# PX4FMUv2_3_SCH1.net
KiCad netlist of a schematic drawn in Altium Designer
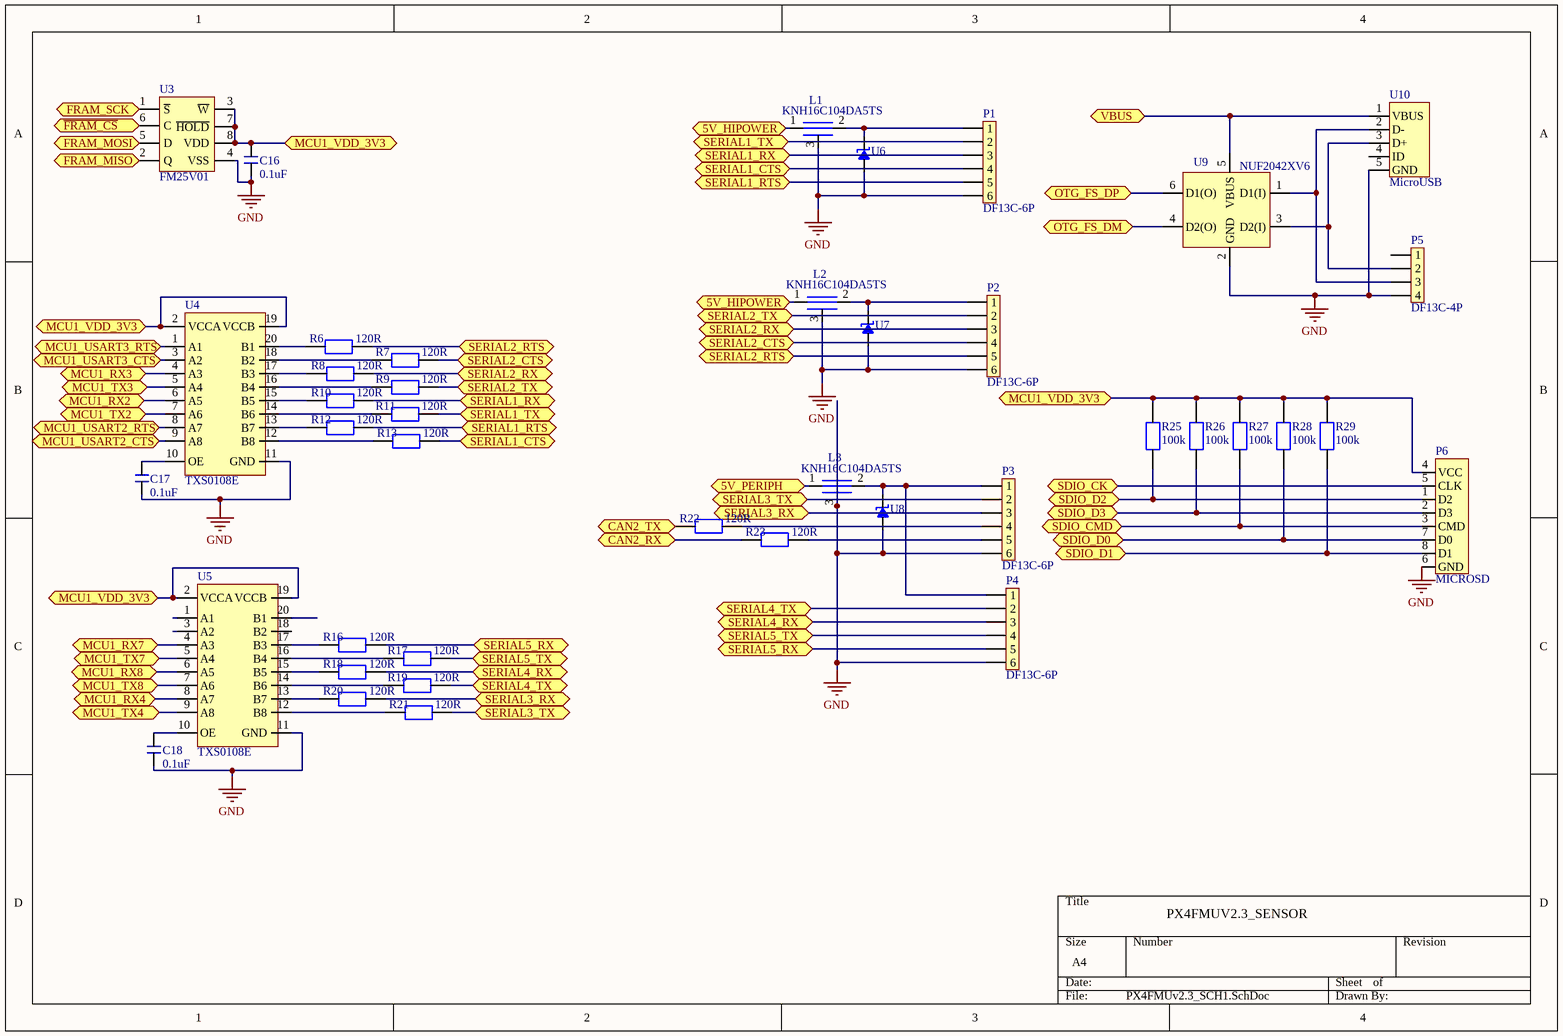
[diagram p0: PX4FMUv2.3_SCH1.SchDoc]

(export (version "E")
  (design (tool "Eeschema 10.0.6"))
  (components
    (comp (ref "C16") (value "0.1uF") (footprint "C 0402") (libsource (lib "px4_SCHLIB") (part "CAP_0402")))
    (comp (ref "C17") (value "0.1uF") (footprint "C 0402") (libsource (lib "px4_SCHLIB") (part "CAP_0402")))
    (comp (ref "C18") (value "0.1uF") (footprint "C 0402") (libsource (lib "px4_SCHLIB") (part "CAP_0402")))
    (comp (ref "L1")
      (value "KNH16C104DA5TS")
      (footprint "KYOCERA-KNH16-DA")
      (libsource (lib "px4_SCHLIB") (part "KNH16C104DA5TS"))
    )
    (comp (ref "L2")
      (value "KNH16C104DA5TS")
      (footprint "KYOCERA-KNH16-DA")
      (libsource (lib "px4_SCHLIB") (part "KNH16C104DA5TS"))
    )
    (comp (ref "L3")
      (value "KNH16C104DA5TS")
      (footprint "KYOCERA-KNH16-DA")
      (libsource (lib "px4_SCHLIB") (part "KNH16C104DA5TS"))
    )
    (comp (ref "P1")
      (value "DF13C-6P")
      (footprint "MX 1.25-LS-6P")
      (libsource (lib "px4_SCHLIB") (part "DF13C-6P"))
    )
    (comp (ref "P2")
      (value "DF13C-6P")
      (footprint "MX 1.25-LS-6P")
      (libsource (lib "px4_SCHLIB") (part "DF13C-6P"))
    )
    (comp (ref "P3")
      (value "DF13C-6P")
      (footprint "MX 1.25-LS-6P")
      (libsource (lib "px4_SCHLIB") (part "DF13C-6P"))
    )
    (comp (ref "P4")
      (value "DF13C-6P")
      (footprint "MX 1.25-LS-6P")
      (libsource (lib "px4_SCHLIB") (part "DF13C-6P"))
    )
    (comp (ref "P5")
      (value "DF13C-4P")
      (footprint "MX 1.25-LS-4P")
      (libsource (lib "px4_SCHLIB") (part "DF13C-4P"))
    )
    (comp (ref "P6") (value "MICROSD") (footprint "microSD") (libsource (lib "px4_SCHLIB") (part "MICROSD")))
    (comp (ref "R6") (value "120R") (footprint "0402R") (libsource (lib "px4_SCHLIB") (part "Res_0402")))
    (comp (ref "R7") (value "120R") (footprint "0402R") (libsource (lib "px4_SCHLIB") (part "Res_0402")))
    (comp (ref "R8") (value "120R") (footprint "0402R") (libsource (lib "px4_SCHLIB") (part "Res_0402")))
    (comp (ref "R9") (value "120R") (footprint "0402R") (libsource (lib "px4_SCHLIB") (part "Res_0402")))
    (comp (ref "R10") (value "120R") (footprint "0402R") (libsource (lib "px4_SCHLIB") (part "Res_0402")))
    (comp (ref "R11") (value "120R") (footprint "0402R") (libsource (lib "px4_SCHLIB") (part "Res_0402")))
    (comp (ref "R12") (value "120R") (footprint "0402R") (libsource (lib "px4_SCHLIB") (part "Res_0402")))
    (comp (ref "R13") (value "120R") (footprint "0402R") (libsource (lib "px4_SCHLIB") (part "Res_0402")))
    (comp (ref "R16") (value "120R") (footprint "0402R") (libsource (lib "px4_SCHLIB") (part "Res_0402")))
    (comp (ref "R17") (value "120R") (footprint "0402R") (libsource (lib "px4_SCHLIB") (part "Res_0402")))
    (comp (ref "R18") (value "120R") (footprint "0402R") (libsource (lib "px4_SCHLIB") (part "Res_0402")))
    (comp (ref "R19") (value "120R") (footprint "0402R") (libsource (lib "px4_SCHLIB") (part "Res_0402")))
    (comp (ref "R20") (value "120R") (footprint "0402R") (libsource (lib "px4_SCHLIB") (part "Res_0402")))
    (comp (ref "R21") (value "120R") (footprint "0402R") (libsource (lib "px4_SCHLIB") (part "Res_0402")))
    (comp (ref "R22") (value "120R") (footprint "0402R") (libsource (lib "px4_SCHLIB") (part "Res_0402")))
    (comp (ref "R23") (value "120R") (footprint "0402R") (libsource (lib "px4_SCHLIB") (part "Res_0402")))
    (comp (ref "R25") (value "100k") (footprint "0402R") (libsource (lib "px4_SCHLIB") (part "Res_0402")))
    (comp (ref "R26") (value "100k") (footprint "0402R") (libsource (lib "px4_SCHLIB") (part "Res_0402")))
    (comp (ref "R27") (value "100k") (footprint "0402R") (libsource (lib "px4_SCHLIB") (part "Res_0402")))
    (comp (ref "R28") (value "100k") (footprint "0402R") (libsource (lib "px4_SCHLIB") (part "Res_0402")))
    (comp (ref "R29") (value "100k") (footprint "0402R") (libsource (lib "px4_SCHLIB") (part "Res_0402")))
    (comp (ref "U3") (value "FM25V01") (footprint "SOIC8") (libsource (lib "px4_SCHLIB") (part "FM25V01")))
    (comp (ref "U4")
      (value "TXS0108E")
      (footprint "PQFN50P450X350X100_HS-21N")
      (libsource (lib "px4_SCHLIB") (part "TXS0108E"))
    )
    (comp (ref "U5")
      (value "TXS0108E")
      (footprint "PQFN50P450X350X100_HS-21N")
      (libsource (lib "px4_SCHLIB") (part "TXS0108E"))
    )
    (comp (ref "U6")
      (value "PESD0402-140")
      (footprint "0402-TVS")
      (libsource (lib "px4_SCHLIB") (part "PESD0402-140"))
    )
    (comp (ref "U7")
      (value "PESD0402-140")
      (footprint "0402-TVS")
      (libsource (lib "px4_SCHLIB") (part "PESD0402-140"))
    )
    (comp (ref "U8")
      (value "PESD0402-140")
      (footprint "0402-TVS")
      (libsource (lib "px4_SCHLIB") (part "PESD0402-140"))
    )
    (comp (ref "U9")
      (value "NUF2042XV6")
      (footprint "SOT563-6")
      (libsource (lib "px4_SCHLIB") (part "NUF2042XV6"))
    )
    (comp (ref "U10")
      (value "MicroUSB")
      (footprint "USB-MICRO_E")
      (libsource (lib "px4_SCHLIB") (part "MicroUSB_SMD"))
    )
  )
  (nets
    (net (code "1") (name "/5V_HIPOWER") (class "Default")
      (node (ref "L1") (pin "1") (pinfunction "1_1") (pintype "passive"))
      (node (ref "L2") (pin "1") (pinfunction "1_1") (pintype "passive"))
    )
    (net (code "2") (name "/5V_PERIPH") (class "Default")
      (node (ref "L3") (pin "1") (pinfunction "1_1") (pintype "passive"))
    )
    (net (code "3") (name "/CAN2_RX") (class "Default")
      (node (ref "R23") (pin "1") (pinfunction "1_1") (pintype "passive"))
    )
    (net (code "4") (name "/CAN2_TX") (class "Default")
      (node (ref "R22") (pin "1") (pinfunction "1_1") (pintype "passive"))
    )
    (net (code "5") (name "/FRAM_MISO") (class "Default")
      (node (ref "U3") (pin "2") (pinfunction "Q_2") (pintype "passive"))
    )
    (net (code "6") (name "/FRAM_MOSI") (class "Default")
      (node (ref "U3") (pin "5") (pinfunction "D_5") (pintype "passive"))
    )
    (net (code "7") (name "/FRAM_SCK") (class "Default")
      (node (ref "U3") (pin "1") (pinfunction "S_1") (pintype "passive"))
    )
    (net (code "8") (name "/MCU1_RX2") (class "Default")
      (node (ref "U4") (pin "6") (pinfunction "A5_6") (pintype "passive"))
    )
    (net (code "9") (name "/MCU1_RX3") (class "Default")
      (node (ref "U4") (pin "4") (pinfunction "A3_4") (pintype "passive"))
    )
    (net (code "10") (name "/MCU1_RX4") (class "Default")
      (node (ref "U5") (pin "8") (pinfunction "A7_8") (pintype "passive"))
    )
    (net (code "11") (name "/MCU1_RX7") (class "Default")
      (node (ref "U5") (pin "4") (pinfunction "A3_4") (pintype "passive"))
    )
    (net (code "12") (name "/MCU1_RX8") (class "Default")
      (node (ref "U5") (pin "6") (pinfunction "A5_6") (pintype "passive"))
    )
    (net (code "13") (name "/MCU1_TX2") (class "Default")
      (node (ref "U4") (pin "7") (pinfunction "A6_7") (pintype "passive"))
    )
    (net (code "14") (name "/MCU1_TX3") (class "Default")
      (node (ref "U4") (pin "5") (pinfunction "A4_5") (pintype "passive"))
    )
    (net (code "15") (name "/MCU1_TX4") (class "Default")
      (node (ref "U5") (pin "9") (pinfunction "A8_9") (pintype "passive"))
    )
    (net (code "16") (name "/MCU1_TX7") (class "Default")
      (node (ref "U5") (pin "5") (pinfunction "A4_5") (pintype "passive"))
    )
    (net (code "17") (name "/MCU1_TX8") (class "Default")
      (node (ref "U5") (pin "7") (pinfunction "A6_7") (pintype "passive"))
    )
    (net (code "18") (name "/MCU1_USART2_CTS") (class "Default")
      (node (ref "U4") (pin "9") (pinfunction "A8_9") (pintype "passive"))
    )
    (net (code "19") (name "/MCU1_USART2_RTS") (class "Default")
      (node (ref "U4") (pin "8") (pinfunction "A7_8") (pintype "passive"))
    )
    (net (code "20") (name "/MCU1_USART3_CTS") (class "Default")
      (node (ref "U4") (pin "3") (pinfunction "A2_3") (pintype "passive"))
    )
    (net (code "21") (name "/MCU1_USART3_RTS") (class "Default")
      (node (ref "U4") (pin "1") (pinfunction "A1_1") (pintype "passive"))
    )
    (net (code "22") (name "/MCU1_VDD_3V3") (class "Default")
      (node (ref "C16") (pin "1") (pinfunction "1_1") (pintype "passive"))
      (node (ref "P6") (pin "4") (pinfunction "VCC_4") (pintype "passive"))
      (node (ref "R25") (pin "2") (pinfunction "2_2") (pintype "passive"))
      (node (ref "R26") (pin "2") (pinfunction "2_2") (pintype "passive"))
      (node (ref "R27") (pin "2") (pinfunction "2_2") (pintype "passive"))
      (node (ref "R28") (pin "2") (pinfunction "2_2") (pintype "passive"))
      (node (ref "R29") (pin "2") (pinfunction "2_2") (pintype "passive"))
      (node (ref "U3") (pin "3") (pinfunction "W_3") (pintype "passive"))
      (node (ref "U3") (pin "7") (pinfunction "HOLD_7") (pintype "passive"))
      (node (ref "U3") (pin "8") (pinfunction "VDD_8") (pintype "passive"))
      (node (ref "U4") (pin "19") (pinfunction "VCCB_19") (pintype "passive"))
      (node (ref "U4") (pin "2") (pinfunction "VCCA_2") (pintype "passive"))
      (node (ref "U5") (pin "19") (pinfunction "VCCB_19") (pintype "passive"))
      (node (ref "U5") (pin "2") (pinfunction "VCCA_2") (pintype "passive"))
    )
    (net (code "23") (name "/OTG_FS_DM") (class "Default")
      (node (ref "U9") (pin "4") (pinfunction "D2(O)_4") (pintype "passive"))
    )
    (net (code "24") (name "/OTG_FS_DP") (class "Default")
      (node (ref "U9") (pin "6") (pinfunction "D1(O)_6") (pintype "passive"))
    )
    (net (code "25") (name "/SDIO_CK") (class "Default")
      (node (ref "P6") (pin "5") (pinfunction "CLK_5") (pintype "passive"))
    )
    (net (code "26") (name "/SDIO_CMD") (class "Default")
      (node (ref "P6") (pin "3") (pinfunction "CMD_3") (pintype "passive"))
      (node (ref "R27") (pin "1") (pinfunction "1_1") (pintype "passive"))
    )
    (net (code "27") (name "/SDIO_D0") (class "Default")
      (node (ref "P6") (pin "7") (pinfunction "D0_7") (pintype "passive"))
      (node (ref "R28") (pin "1") (pinfunction "1_1") (pintype "passive"))
    )
    (net (code "28") (name "/SDIO_D1") (class "Default")
      (node (ref "P6") (pin "8") (pinfunction "D1_8") (pintype "passive"))
      (node (ref "R29") (pin "1") (pinfunction "1_1") (pintype "passive"))
    )
    (net (code "29") (name "/SDIO_D2") (class "Default")
      (node (ref "P6") (pin "1") (pinfunction "D2_1") (pintype "passive"))
      (node (ref "R25") (pin "1") (pinfunction "1_1") (pintype "passive"))
    )
    (net (code "30") (name "/SDIO_D3") (class "Default")
      (node (ref "P6") (pin "2") (pinfunction "D3_2") (pintype "passive"))
      (node (ref "R26") (pin "1") (pinfunction "1_1") (pintype "passive"))
    )
    (net (code "31") (name "/SERIAL1_CTS") (class "Default")
      (node (ref "P1") (pin "4") (pinfunction "4_4") (pintype "passive"))
      (node (ref "R13") (pin "2") (pinfunction "2_2") (pintype "passive"))
    )
    (net (code "32") (name "/SERIAL1_RTS") (class "Default")
      (node (ref "P1") (pin "5") (pinfunction "5_5") (pintype "passive"))
      (node (ref "R12") (pin "2") (pinfunction "2_2") (pintype "passive"))
    )
    (net (code "33") (name "/SERIAL1_RX") (class "Default")
      (node (ref "P1") (pin "3") (pinfunction "3_3") (pintype "passive"))
      (node (ref "R10") (pin "2") (pinfunction "2_2") (pintype "passive"))
    )
    (net (code "34") (name "/SERIAL1_TX") (class "Default")
      (node (ref "P1") (pin "2") (pinfunction "2_2") (pintype "passive"))
      (node (ref "R11") (pin "2") (pinfunction "2_2") (pintype "passive"))
    )
    (net (code "35") (name "/SERIAL2_CTS") (class "Default")
      (node (ref "P2") (pin "4") (pinfunction "4_4") (pintype "passive"))
      (node (ref "R7") (pin "2") (pinfunction "2_2") (pintype "passive"))
    )
    (net (code "36") (name "/SERIAL2_RTS") (class "Default")
      (node (ref "P2") (pin "5") (pinfunction "5_5") (pintype "passive"))
      (node (ref "R6") (pin "2") (pinfunction "2_2") (pintype "passive"))
    )
    (net (code "37") (name "/SERIAL2_RX") (class "Default")
      (node (ref "P2") (pin "3") (pinfunction "3_3") (pintype "passive"))
      (node (ref "R8") (pin "2") (pinfunction "2_2") (pintype "passive"))
    )
    (net (code "38") (name "/SERIAL2_TX") (class "Default")
      (node (ref "P2") (pin "2") (pinfunction "2_2") (pintype "passive"))
      (node (ref "R9") (pin "2") (pinfunction "2_2") (pintype "passive"))
    )
    (net (code "39") (name "/SERIAL3_RX") (class "Default")
      (node (ref "P3") (pin "3") (pinfunction "3_3") (pintype "passive"))
      (node (ref "R20") (pin "2") (pinfunction "2_2") (pintype "passive"))
    )
    (net (code "40") (name "/SERIAL3_TX") (class "Default")
      (node (ref "P3") (pin "2") (pinfunction "2_2") (pintype "passive"))
      (node (ref "R21") (pin "2") (pinfunction "2_2") (pintype "passive"))
    )
    (net (code "41") (name "/SERIAL4_RX") (class "Default")
      (node (ref "P4") (pin "3") (pinfunction "3_3") (pintype "passive"))
      (node (ref "R18") (pin "2") (pinfunction "2_2") (pintype "passive"))
    )
    (net (code "42") (name "/SERIAL4_TX") (class "Default")
      (node (ref "P4") (pin "2") (pinfunction "2_2") (pintype "passive"))
      (node (ref "R19") (pin "2") (pinfunction "2_2") (pintype "passive"))
    )
    (net (code "43") (name "/SERIAL5_RX") (class "Default")
      (node (ref "P4") (pin "5") (pinfunction "5_5") (pintype "passive"))
      (node (ref "R16") (pin "2") (pinfunction "2_2") (pintype "passive"))
    )
    (net (code "44") (name "/SERIAL5_TX") (class "Default")
      (node (ref "P4") (pin "4") (pinfunction "4_4") (pintype "passive"))
      (node (ref "R17") (pin "2") (pinfunction "2_2") (pintype "passive"))
    )
    (net (code "45") (name "/VBUS") (class "Default")
      (node (ref "U10") (pin "1") (pinfunction "VBUS_1") (pintype "passive"))
      (node (ref "U9") (pin "5") (pinfunction "VBUS_5") (pintype "passive"))
    )
    (net (code "46") (name "/~{FRAM_CS}") (class "Default")
      (node (ref "U3") (pin "6") (pinfunction "C_6") (pintype "passive"))
    )
    (net (code "47") (name "GND") (class "Default")
      (node (ref "C16") (pin "2") (pinfunction "2_2") (pintype "passive"))
      (node (ref "C17") (pin "2") (pinfunction "2_2") (pintype "passive"))
      (node (ref "C18") (pin "2") (pinfunction "2_2") (pintype "passive"))
      (node (ref "L1") (pin "3") (pinfunction "3_3") (pintype "passive"))
      (node (ref "L2") (pin "3") (pinfunction "3_3") (pintype "passive"))
      (node (ref "L3") (pin "3") (pinfunction "3_3") (pintype "passive"))
      (node (ref "P1") (pin "6") (pinfunction "6_6") (pintype "passive"))
      (node (ref "P2") (pin "6") (pinfunction "6_6") (pintype "passive"))
      (node (ref "P3") (pin "6") (pinfunction "6_6") (pintype "passive"))
      (node (ref "P4") (pin "6") (pinfunction "6_6") (pintype "passive"))
      (node (ref "P5") (pin "4") (pinfunction "4_4") (pintype "passive"))
      (node (ref "P6") (pin "6") (pinfunction "GND_6") (pintype "passive"))
      (node (ref "U10") (pin "5") (pinfunction "GND_5") (pintype "passive"))
      (node (ref "U3") (pin "4") (pinfunction "VSS_4") (pintype "passive"))
      (node (ref "U4") (pin "11") (pinfunction "GND_11") (pintype "passive"))
      (node (ref "U5") (pin "11") (pinfunction "GND_11") (pintype "passive"))
      (node (ref "U6") (pin "1") (pinfunction "1_1") (pintype "passive"))
      (node (ref "U7") (pin "1") (pinfunction "1_1") (pintype "passive"))
      (node (ref "U8") (pin "1") (pinfunction "1_1") (pintype "passive"))
      (node (ref "U9") (pin "2") (pinfunction "GND_2") (pintype "passive"))
    )
    (net (code "48") (name "Net-(L1-Pad2)") (class "Default")
      (node (ref "L1") (pin "2") (pinfunction "2_2") (pintype "passive"))
      (node (ref "P1") (pin "1") (pinfunction "1_1") (pintype "passive"))
      (node (ref "U6") (pin "2") (pinfunction "2_2") (pintype "passive"))
    )
    (net (code "49") (name "Net-(L2-Pad2)") (class "Default")
      (node (ref "L2") (pin "2") (pinfunction "2_2") (pintype "passive"))
      (node (ref "P2") (pin "1") (pinfunction "1_1") (pintype "passive"))
      (node (ref "U7") (pin "2") (pinfunction "2_2") (pintype "passive"))
    )
    (net (code "50") (name "Net-(L3-Pad2)") (class "Default")
      (node (ref "L3") (pin "2") (pinfunction "2_2") (pintype "passive"))
      (node (ref "P3") (pin "1") (pinfunction "1_1") (pintype "passive"))
      (node (ref "P4") (pin "1") (pinfunction "1_1") (pintype "passive"))
      (node (ref "U8") (pin "2") (pinfunction "2_2") (pintype "passive"))
    )
    (net (code "51") (name "Net-(P3-Pad4)") (class "Default")
      (node (ref "P3") (pin "4") (pinfunction "4_4") (pintype "passive"))
      (node (ref "R22") (pin "2") (pinfunction "2_2") (pintype "passive"))
    )
    (net (code "52") (name "Net-(P3-Pad5)") (class "Default")
      (node (ref "P3") (pin "5") (pinfunction "5_5") (pintype "passive"))
      (node (ref "R23") (pin "2") (pinfunction "2_2") (pintype "passive"))
    )
    (net (code "53") (name "Net-(U4-B1)") (class "Default")
      (node (ref "R6") (pin "1") (pinfunction "1_1") (pintype "passive"))
      (node (ref "U4") (pin "20") (pinfunction "B1_20") (pintype "passive"))
    )
    (net (code "54") (name "Net-(U4-B2)") (class "Default")
      (node (ref "R7") (pin "1") (pinfunction "1_1") (pintype "passive"))
      (node (ref "U4") (pin "18") (pinfunction "B2_18") (pintype "passive"))
    )
    (net (code "55") (name "Net-(U4-B3)") (class "Default")
      (node (ref "R8") (pin "1") (pinfunction "1_1") (pintype "passive"))
      (node (ref "U4") (pin "17") (pinfunction "B3_17") (pintype "passive"))
    )
    (net (code "56") (name "Net-(U4-B4)") (class "Default")
      (node (ref "R9") (pin "1") (pinfunction "1_1") (pintype "passive"))
      (node (ref "U4") (pin "16") (pinfunction "B4_16") (pintype "passive"))
    )
    (net (code "57") (name "Net-(U4-B5)") (class "Default")
      (node (ref "R10") (pin "1") (pinfunction "1_1") (pintype "passive"))
      (node (ref "U4") (pin "15") (pinfunction "B5_15") (pintype "passive"))
    )
    (net (code "58") (name "Net-(U4-B6)") (class "Default")
      (node (ref "R11") (pin "1") (pinfunction "1_1") (pintype "passive"))
      (node (ref "U4") (pin "14") (pinfunction "B6_14") (pintype "passive"))
    )
    (net (code "59") (name "Net-(U4-B7)") (class "Default")
      (node (ref "R12") (pin "1") (pinfunction "1_1") (pintype "passive"))
      (node (ref "U4") (pin "13") (pinfunction "B7_13") (pintype "passive"))
    )
    (net (code "60") (name "Net-(U4-B8)") (class "Default")
      (node (ref "R13") (pin "1") (pinfunction "1_1") (pintype "passive"))
      (node (ref "U4") (pin "12") (pinfunction "B8_12") (pintype "passive"))
    )
    (net (code "61") (name "Net-(U4-OE)") (class "Default")
      (node (ref "C17") (pin "1") (pinfunction "1_1") (pintype "passive"))
      (node (ref "U4") (pin "10") (pinfunction "OE_10") (pintype "passive"))
    )
    (net (code "62") (name "Net-(U5-B3)") (class "Default")
      (node (ref "R16") (pin "1") (pinfunction "1_1") (pintype "passive"))
      (node (ref "U5") (pin "17") (pinfunction "B3_17") (pintype "passive"))
    )
    (net (code "63") (name "Net-(U5-B4)") (class "Default")
      (node (ref "R17") (pin "1") (pinfunction "1_1") (pintype "passive"))
      (node (ref "U5") (pin "16") (pinfunction "B4_16") (pintype "passive"))
    )
    (net (code "64") (name "Net-(U5-B5)") (class "Default")
      (node (ref "R18") (pin "1") (pinfunction "1_1") (pintype "passive"))
      (node (ref "U5") (pin "15") (pinfunction "B5_15") (pintype "passive"))
    )
    (net (code "65") (name "Net-(U5-B6)") (class "Default")
      (node (ref "R19") (pin "1") (pinfunction "1_1") (pintype "passive"))
      (node (ref "U5") (pin "14") (pinfunction "B6_14") (pintype "passive"))
    )
    (net (code "66") (name "Net-(U5-B7)") (class "Default")
      (node (ref "R20") (pin "1") (pinfunction "1_1") (pintype "passive"))
      (node (ref "U5") (pin "13") (pinfunction "B7_13") (pintype "passive"))
    )
    (net (code "67") (name "Net-(U5-B8)") (class "Default")
      (node (ref "R21") (pin "1") (pinfunction "1_1") (pintype "passive"))
      (node (ref "U5") (pin "12") (pinfunction "B8_12") (pintype "passive"))
    )
    (net (code "68") (name "Net-(U5-OE)") (class "Default")
      (node (ref "C18") (pin "1") (pinfunction "1_1") (pintype "passive"))
      (node (ref "U5") (pin "10") (pinfunction "OE_10") (pintype "passive"))
    )
    (net (code "69") (name "Net-(U10-D+)") (class "Default")
      (node (ref "P5") (pin "2") (pinfunction "2_2") (pintype "passive"))
      (node (ref "U10") (pin "3") (pinfunction "D+_3") (pintype "passive"))
      (node (ref "U9") (pin "3") (pinfunction "D2(I)_3") (pintype "passive"))
    )
    (net (code "70") (name "Net-(U10-D-)") (class "Default")
      (node (ref "P5") (pin "3") (pinfunction "3_3") (pintype "passive"))
      (node (ref "U10") (pin "2") (pinfunction "D-_2") (pintype "passive"))
      (node (ref "U9") (pin "1") (pinfunction "D1(I)_1") (pintype "passive"))
    )
    (net (code "71") (name "unconnected-(P5-Pad1)") (class "Default")
      (node (ref "P5") (pin "1") (pinfunction "1_1") (pintype "passive"))
    )
    (net (code "72") (name "unconnected-(U5-A1-Pad1)") (class "Default")
      (node (ref "U5") (pin "1") (pinfunction "A1_1") (pintype "passive"))
    )
    (net (code "73") (name "unconnected-(U5-A2-Pad3)") (class "Default")
      (node (ref "U5") (pin "3") (pinfunction "A2_3") (pintype "passive"))
    )
    (net (code "74") (name "unconnected-(U5-B1-Pad20)") (class "Default")
      (node (ref "U5") (pin "20") (pinfunction "B1_20") (pintype "passive"))
    )
    (net (code "75") (name "unconnected-(U5-B2-Pad18)") (class "Default")
      (node (ref "U5") (pin "18") (pinfunction "B2_18") (pintype "passive"))
    )
    (net (code "76") (name "unconnected-(U10-ID-Pad4)") (class "Default")
      (node (ref "U10") (pin "4") (pinfunction "ID_4") (pintype "passive"))
    )
  )
)
